# SunS_RTD_Interface.net
KiCad netlist of a schematic drawn in Altium Designer
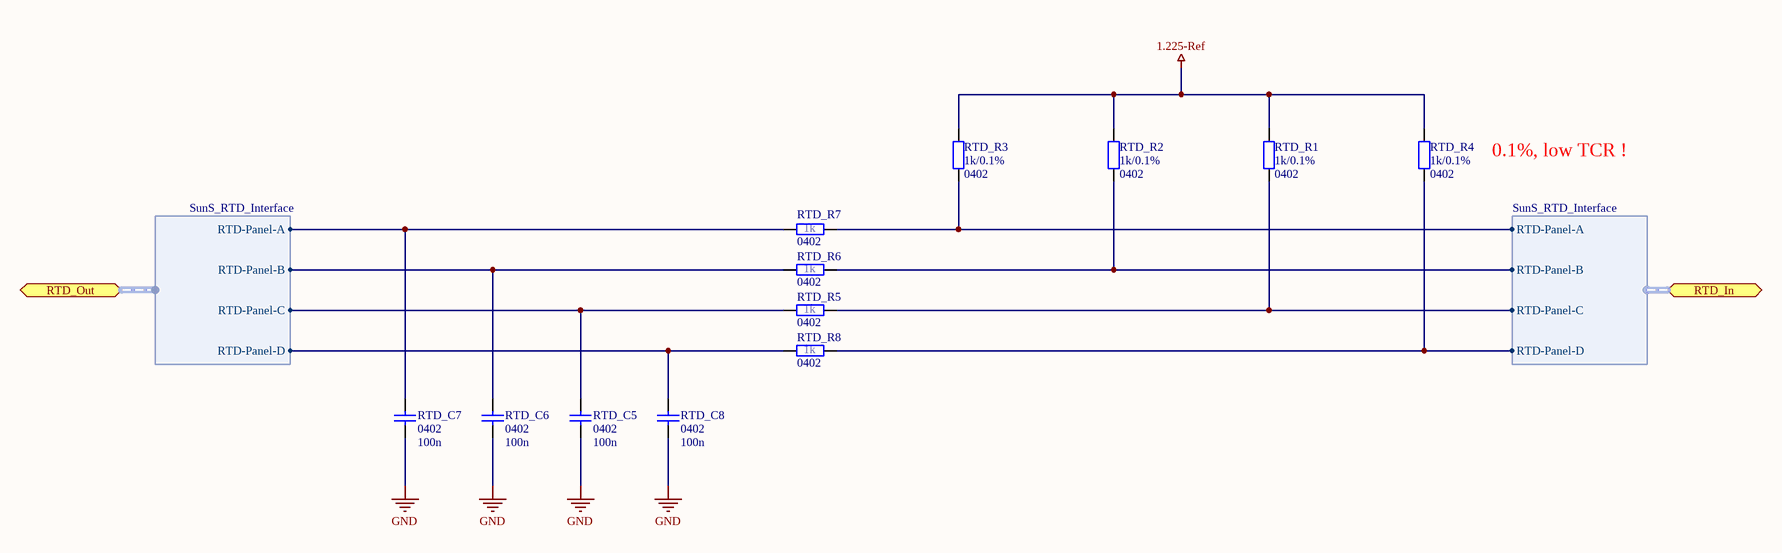
[diagram p0: SunS_RTD_Interface.SchDoc]

(export (version "E")
  (design (tool "Eeschema 10.0.6"))
  (components
    (comp (ref "RTD_C5")
      (value "0402")
      (footprint "SMD_Capacitor_0402")
      (description "Capacitor")
      (fields (field (name "ALTIUM_VALUE") "100n") (field (name "PUBLISHER") "Altium Limited"))
      (libsource (lib "Miscellaneous Devices") (part "Cap"))
    )
    (comp (ref "RTD_C6")
      (value "0402")
      (footprint "SMD_Capacitor_0402")
      (description "Capacitor")
      (fields (field (name "ALTIUM_VALUE") "100n") (field (name "PUBLISHER") "Altium Limited"))
      (libsource (lib "Miscellaneous Devices") (part "Cap"))
    )
    (comp (ref "RTD_C7")
      (value "0402")
      (footprint "SMD_Capacitor_0402")
      (description "Capacitor")
      (fields (field (name "ALTIUM_VALUE") "100n") (field (name "PUBLISHER") "Altium Limited"))
      (libsource (lib "Miscellaneous Devices") (part "Cap"))
    )
    (comp (ref "RTD_C8")
      (value "0402")
      (footprint "SMD_Capacitor_0402")
      (description "Capacitor")
      (fields (field (name "ALTIUM_VALUE") "100n") (field (name "PUBLISHER") "Altium Limited"))
      (libsource (lib "Miscellaneous Devices") (part "Cap"))
    )
    (comp (ref "RTD_R1")
      (value "1k/0.1%")
      (footprint "SMD_Resistor_0402")
      (description "1k/1% Vishay CRCW 0402 Resistor. 63mW, 100ppm, 50V.")
      (fields
        (field (name "MANUFACTURER") "Vishay")
        (field (name "MANUFACTURERPARTNUMBER") "CRCW04021K00FKxxxx")
        (field (name "PACKAGE") "0402")
      )
      (libsource (lib "resistors") (part "CRCW04021K00FKxxxx"))
    )
    (comp (ref "RTD_R2")
      (value "1k/0.1%")
      (footprint "SMD_Resistor_0402")
      (description "1k/1% Vishay CRCW 0402 Resistor. 63mW, 100ppm, 50V.")
      (fields
        (field (name "MANUFACTURER") "Vishay")
        (field (name "MANUFACTURERPARTNUMBER") "CRCW04021K00FKxxxx")
        (field (name "PACKAGE") "0402")
      )
      (libsource (lib "resistors") (part "CRCW04021K00FKxxxx"))
    )
    (comp (ref "RTD_R3")
      (value "1k/0.1%")
      (footprint "SMD_Resistor_0402")
      (description "1k/1% Vishay CRCW 0402 Resistor. 63mW, 100ppm, 50V.")
      (fields
        (field (name "MANUFACTURER") "Vishay")
        (field (name "MANUFACTURERPARTNUMBER") "CRCW04021K00FKxxxx")
        (field (name "PACKAGE") "0402")
      )
      (libsource (lib "resistors") (part "CRCW04021K00FKxxxx"))
    )
    (comp (ref "RTD_R4")
      (value "1k/0.1%")
      (footprint "SMD_Resistor_0402")
      (description "1k/1% Vishay CRCW 0402 Resistor. 63mW, 100ppm, 50V.")
      (fields
        (field (name "MANUFACTURER") "Vishay")
        (field (name "MANUFACTURERPARTNUMBER") "CRCW04021K00FKxxxx")
        (field (name "PACKAGE") "0402")
      )
      (libsource (lib "resistors") (part "CRCW04021K00FKxxxx"))
    )
    (comp (ref "RTD_R5")
      (value "1k")
      (footprint "SMD_Resistor_0402")
      (description "1k/1% Vishay CRCW 0402 Resistor. 63mW, 100ppm, 50V.")
      (fields
        (field (name "MANUFACTURER") "Vishay")
        (field (name "MANUFACTURERPARTNUMBER") "CRCW04021K00FKxxxx")
        (field (name "PACKAGE") "0402")
      )
      (libsource (lib "resistors") (part "CRCW04021K00FKxxxx"))
    )
    (comp (ref "RTD_R6")
      (value "1k")
      (footprint "SMD_Resistor_0402")
      (description "1k/1% Vishay CRCW 0402 Resistor. 63mW, 100ppm, 50V.")
      (fields
        (field (name "MANUFACTURER") "Vishay")
        (field (name "MANUFACTURERPARTNUMBER") "CRCW04021K00FKxxxx")
        (field (name "PACKAGE") "0402")
      )
      (libsource (lib "resistors") (part "CRCW04021K00FKxxxx"))
    )
    (comp (ref "RTD_R7")
      (value "1k")
      (footprint "SMD_Resistor_0402")
      (description "1k/1% Vishay CRCW 0402 Resistor. 63mW, 100ppm, 50V.")
      (fields
        (field (name "MANUFACTURER") "Vishay")
        (field (name "MANUFACTURERPARTNUMBER") "CRCW04021K00FKxxxx")
        (field (name "PACKAGE") "0402")
      )
      (libsource (lib "resistors") (part "CRCW04021K00FKxxxx"))
    )
    (comp (ref "RTD_R8")
      (value "1k")
      (footprint "SMD_Resistor_0402")
      (description "1k/1% Vishay CRCW 0402 Resistor. 63mW, 100ppm, 50V.")
      (fields
        (field (name "MANUFACTURER") "Vishay")
        (field (name "MANUFACTURERPARTNUMBER") "CRCW04021K00FKxxxx")
        (field (name "PACKAGE") "0402")
      )
      (libsource (lib "resistors") (part "CRCW04021K00FKxxxx"))
    )
  )
  (nets
    (net (code "3") (name "1.225-Ref") (class "Default")
      (node (ref "RTD_R1") (pin "1") (pinfunction "1_1") (pintype "passive"))
      (node (ref "RTD_R2") (pin "1") (pinfunction "1_1") (pintype "passive"))
      (node (ref "RTD_R3") (pin "1") (pinfunction "1_1") (pintype "passive"))
      (node (ref "RTD_R4") (pin "1") (pinfunction "1_1") (pintype "passive"))
    )
    (net (code "4") (name "GND") (class "Default")
      (node (ref "RTD_C5") (pin "1") (pinfunction "1_1") (pintype "passive"))
      (node (ref "RTD_C6") (pin "1") (pinfunction "1_1") (pintype "passive"))
      (node (ref "RTD_C7") (pin "1") (pinfunction "1_1") (pintype "passive"))
      (node (ref "RTD_C8") (pin "1") (pinfunction "1_1") (pintype "passive"))
    )
    (net (code "5") (name "Net-(RTD_C5-Pad2)") (class "Default")
      (node (ref "RTD_C5") (pin "2") (pinfunction "2_2") (pintype "passive"))
      (node (ref "RTD_R5") (pin "2") (pinfunction "2_2") (pintype "passive"))
    )
    (net (code "6") (name "Net-(RTD_C6-Pad2)") (class "Default")
      (node (ref "RTD_C6") (pin "2") (pinfunction "2_2") (pintype "passive"))
      (node (ref "RTD_R6") (pin "2") (pinfunction "2_2") (pintype "passive"))
    )
    (net (code "7") (name "Net-(RTD_C7-Pad2)") (class "Default")
      (node (ref "RTD_C7") (pin "2") (pinfunction "2_2") (pintype "passive"))
      (node (ref "RTD_R7") (pin "2") (pinfunction "2_2") (pintype "passive"))
    )
    (net (code "8") (name "Net-(RTD_C8-Pad2)") (class "Default")
      (node (ref "RTD_C8") (pin "2") (pinfunction "2_2") (pintype "passive"))
      (node (ref "RTD_R8") (pin "2") (pinfunction "2_2") (pintype "passive"))
    )
    (net (code "9") (name "Net-(RTD_R1-Pad2)") (class "Default")
      (node (ref "RTD_R1") (pin "2") (pinfunction "2_2") (pintype "passive"))
      (node (ref "RTD_R5") (pin "1") (pinfunction "1_1") (pintype "passive"))
    )
    (net (code "10") (name "Net-(RTD_R2-Pad2)") (class "Default")
      (node (ref "RTD_R2") (pin "2") (pinfunction "2_2") (pintype "passive"))
      (node (ref "RTD_R6") (pin "1") (pinfunction "1_1") (pintype "passive"))
    )
    (net (code "11") (name "Net-(RTD_R3-Pad2)") (class "Default")
      (node (ref "RTD_R3") (pin "2") (pinfunction "2_2") (pintype "passive"))
      (node (ref "RTD_R7") (pin "1") (pinfunction "1_1") (pintype "passive"))
    )
    (net (code "12") (name "Net-(RTD_R4-Pad2)") (class "Default")
      (node (ref "RTD_R4") (pin "2") (pinfunction "2_2") (pintype "passive"))
      (node (ref "RTD_R8") (pin "1") (pinfunction "1_1") (pintype "passive"))
    )
  )
)
